# 08-MagnetSensor.net
KiCad netlist of a schematic drawn in Altium Designer
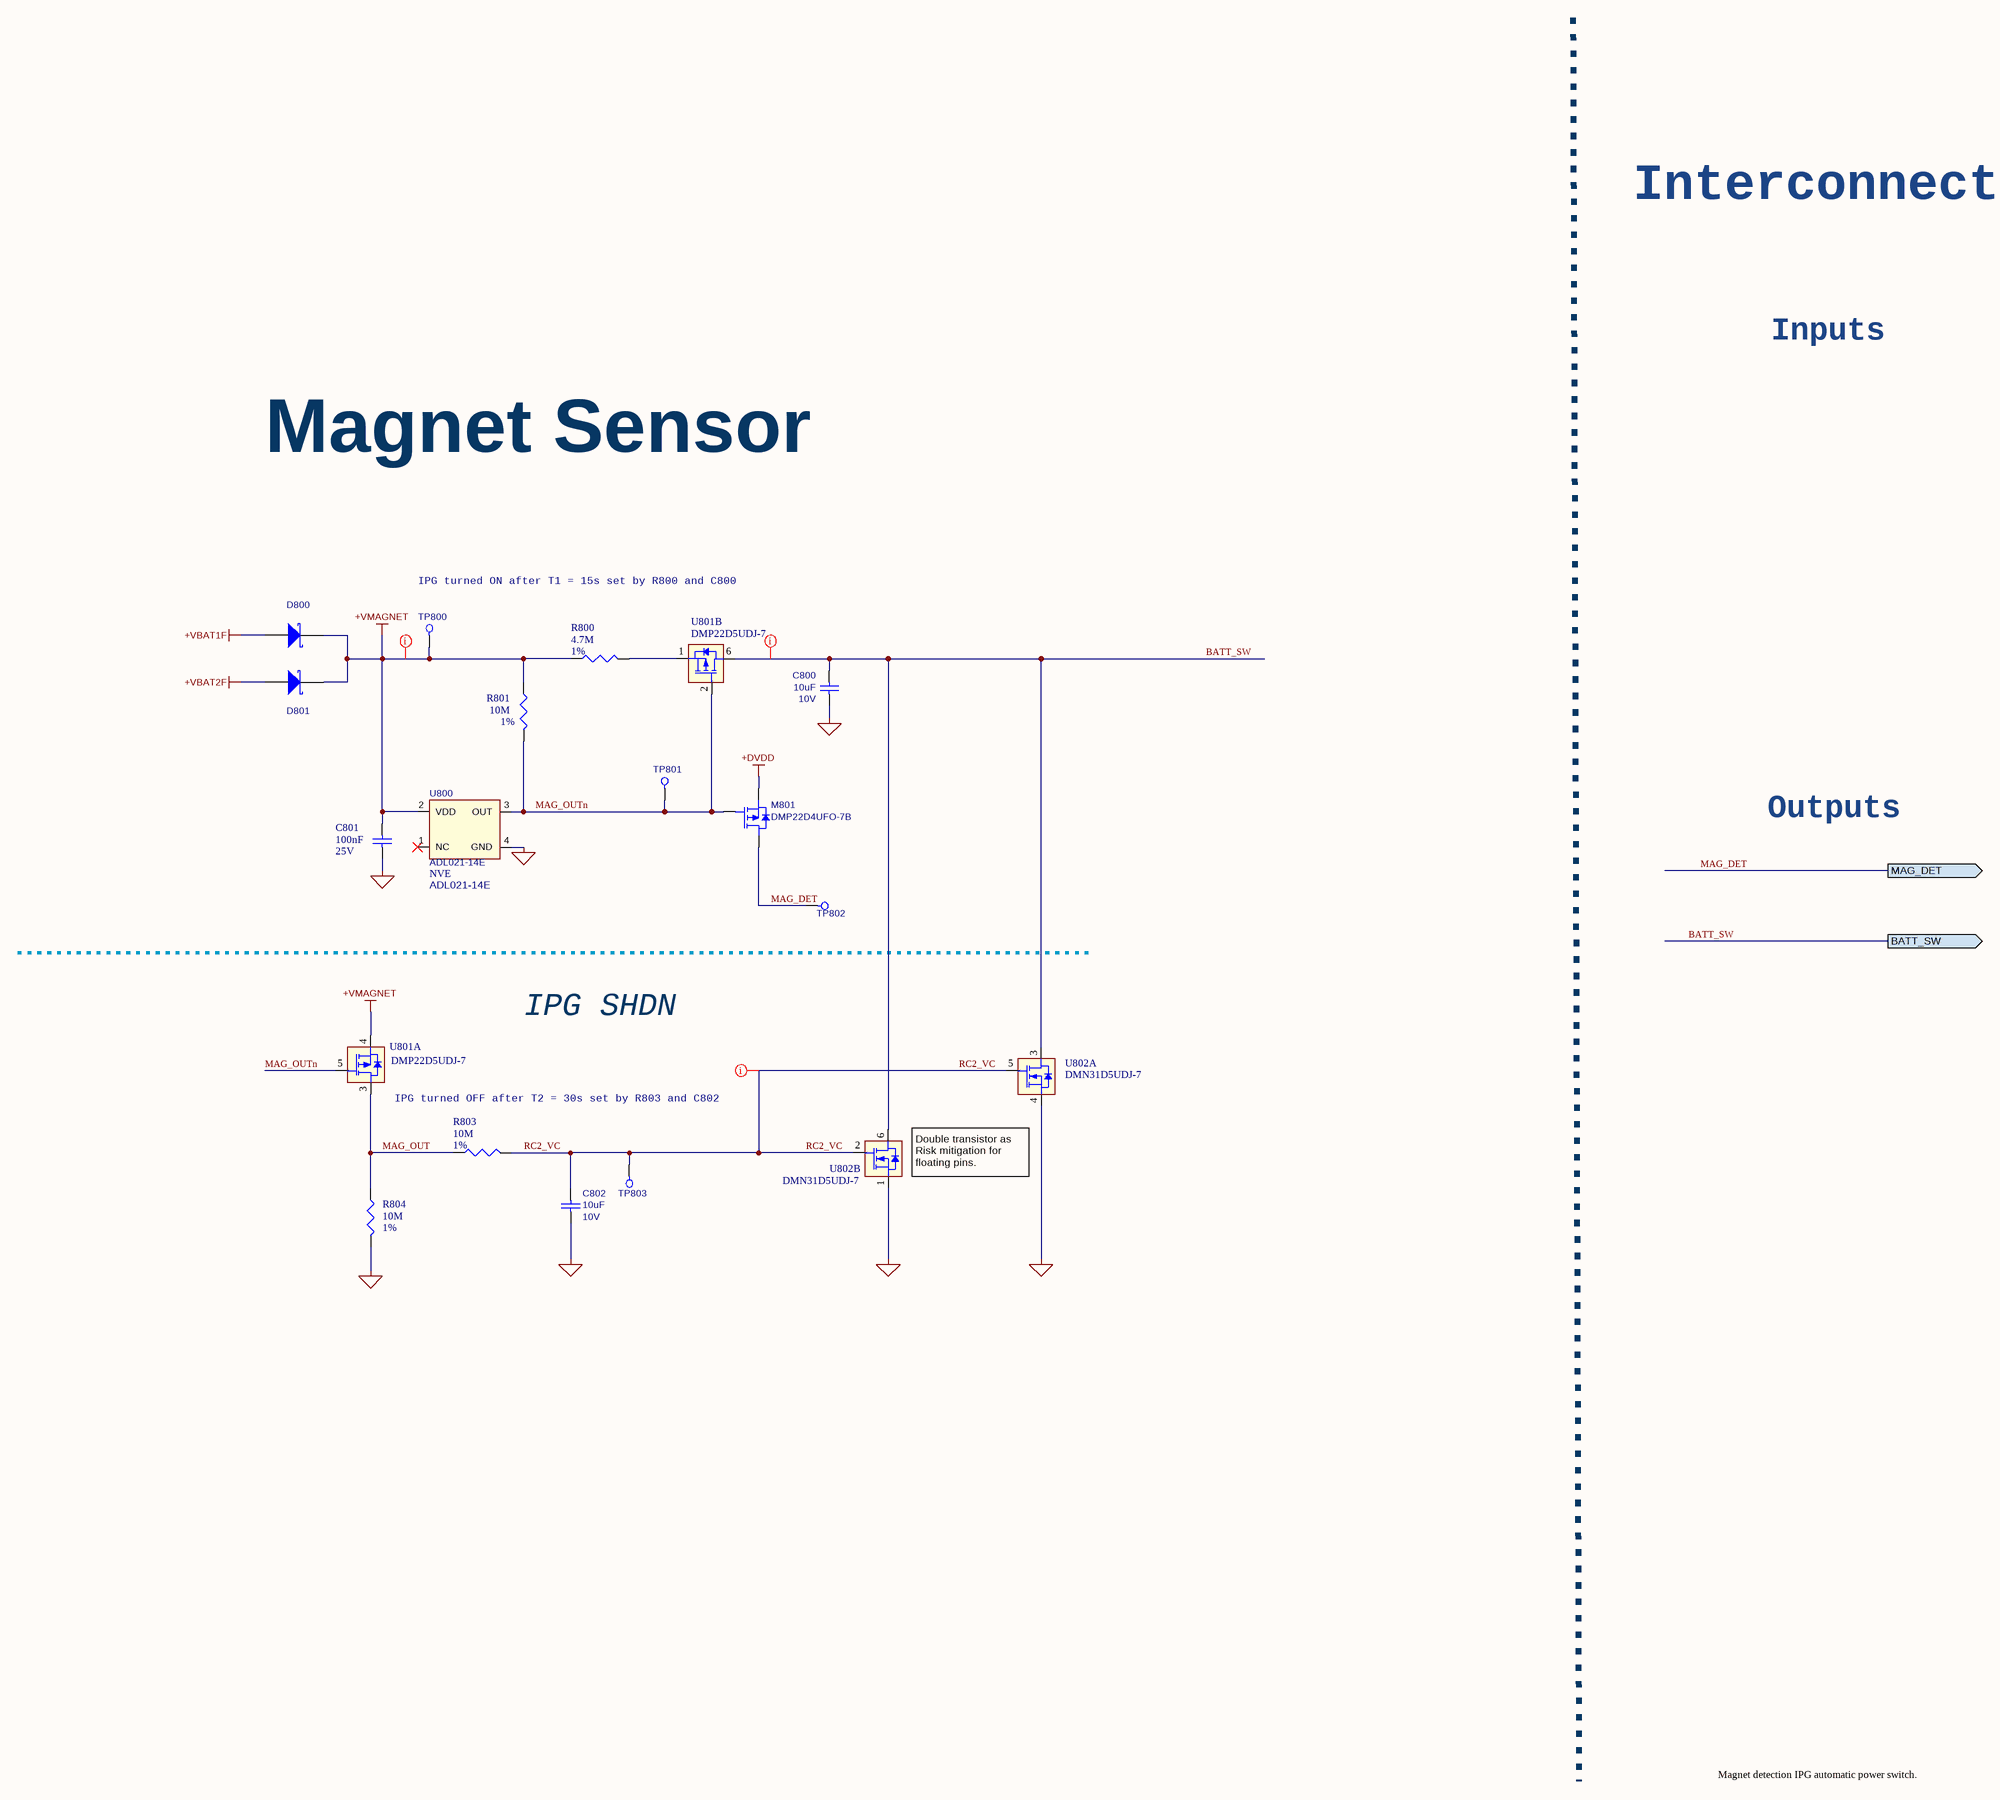
[diagram p0: 08-MagnetSensor.SchDoc]

(export (version "E")
  (design (tool "Eeschema 10.0.6"))
  (components
    (comp (ref "C800")
      (value "10uF")
      (footprint "CAP0402_REDUCED")
      (description "Capacitor, 10uf, X5R, 10V, 20%, 0402, Implant-grade")
      (fields
        (field (name "MANUFACTURER") "Murata")
        (field (name "RATING") "10V")
        (field (name "MANUFACTURER PART NUMBER") "ZRB15XR61A106ME01D")
      )
      (libsource (lib "MP-LIBRARY") (part "ZRB15XR61A106ME01D"))
    )
    (comp (ref "C801")
      (value "100nF")
      (footprint "C0201_C")
      (fields
        (field (name "MANUFACTURER") "Murata")
        (field (name "MANUFACTURER PART NUMBER") "GRM033R61E104KE14J")
        (field (name "RATED DC VOLTAGE (URDC)") "25V")
      )
      (libsource (lib "MP-LIBRARY") (part "GRM033R61E104KE14J"))
    )
    (comp (ref "C802")
      (value "10uF")
      (footprint "CAP0402_REDUCED")
      (description "Capacitor, 10uf, X5R, 10V, 20%, 0402, Implant-grade")
      (fields
        (field (name "MANUFACTURER") "Murata")
        (field (name "RATING") "10V")
        (field (name "MANUFACTURER PART NUMBER") "ZRB15XR61A106ME01D")
      )
      (libsource (lib "MP-LIBRARY") (part "ZRB15XR61A106ME01D"))
    )
    (comp (ref "D800")
      (value "NSR0130P2T5G")
      (footprint "ONSC_SOD-923_CASE514AB")
      (description "Schottky, 30V, 100mA, 385mV, 200mW, SOD-923")
      (fields (field (name "MANUFACTURER") "ON Semiconductor"))
      (libsource (lib "MP-LIBRARY") (part "NSR0130P2T5G"))
    )
    (comp (ref "D801")
      (value "NSR0130P2T5G")
      (footprint "ONSC_SOD-923_CASE514AB")
      (description "Schottky, 30V, 100mA, 385mV, 200mW, SOD-923")
      (fields (field (name "MANUFACTURER") "ON Semiconductor"))
      (libsource (lib "MP-LIBRARY") (part "NSR0130P2T5G"))
    )
    (comp (ref "M801")
      (value "DMP22D4UFO-7B")
      (footprint "DIODESINC_X2-DFN0604-3")
      (description "MOSFET, P-chan, -20V, -383mA, DFN0604")
      (fields (field (name "MANUFACTURER") "Diodes Inc"))
      (libsource (lib "MP-LIBRARY") (part "DMP22D4UFO-7B"))
    )
    (comp (ref "R800")
      (value "4.7M")
      (footprint "R0201_C")
      (fields
        (field (name "MANUFACTURER") "Vishay Dale")
        (field (name "MANUFACTURER PART NUMBER") "CRCW02014M70FNED")
        (field (name "TOLERANCE") "1%")
        (field (name "POWER") "50mW")
      )
      (libsource (lib "MP-LIBRARY") (part "CRCW02014M70FNED"))
    )
    (comp (ref "R801")
      (value "10M")
      (footprint "R0201_C")
      (fields
        (field (name "MANUFACTURER") "Vishay Draloric")
        (field (name "MANUFACTURER PART NUMBER") "CRCW020110M0FNED")
        (field (name "TOLERANCE") "1%")
        (field (name "POWER") "50mW")
      )
      (libsource (lib "MP-LIBRARY") (part "CRCW020110M0FNED"))
    )
    (comp (ref "R803")
      (value "10M")
      (footprint "R0201_C")
      (fields
        (field (name "MANUFACTURER") "Vishay Draloric")
        (field (name "MANUFACTURER PART NUMBER") "CRCW020110M0FNED")
        (field (name "TOLERANCE") "1%")
        (field (name "POWER") "50mW")
      )
      (libsource (lib "MP-LIBRARY") (part "CRCW020110M0FNED"))
    )
    (comp (ref "R804")
      (value "10M")
      (footprint "R0201_C")
      (fields
        (field (name "MANUFACTURER") "Vishay Draloric")
        (field (name "MANUFACTURER PART NUMBER") "CRCW020110M0FNED")
        (field (name "TOLERANCE") "1%")
        (field (name "POWER") "50mW")
      )
      (libsource (lib "MP-LIBRARY") (part "CRCW020110M0FNED"))
    )
    (comp (ref "TP800")
      (value "Test Point")
      (footprint "testpad_0.9mm")
      (description "Test pad, 0.90mm circular pad")
      (libsource (lib "MP-LIBRARY") (part "Test Point"))
    )
    (comp (ref "TP801")
      (value "Test Point")
      (footprint "testpad_0.9mm")
      (description "Test pad, 0.90mm circular pad")
      (libsource (lib "MP-LIBRARY") (part "Test Point"))
    )
    (comp (ref "TP802")
      (value "Test Point")
      (footprint "testpad_0.9mm")
      (description "Test pad, 0.90mm circular pad")
      (libsource (lib "MP-LIBRARY") (part "Test Point"))
    )
    (comp (ref "TP803")
      (value "Test Point")
      (footprint "testpad_0.9mm")
      (description "Test pad, 0.90mm circular pad")
      (libsource (lib "MP-LIBRARY") (part "Test Point"))
    )
    (comp (ref "U800")
      (value "ADL021-14E")
      (footprint "NVE_ULLGA4")
      (description "Magnet Sensor, 15 Gauss, ULLGA4, Implant-grade")
      (fields (field (name "MANUFACTURER") "NVE") (field (name "ALTIUM_VALUE") "ADL021-14E"))
      (libsource (lib "MP-LIBRARY") (part "ADL021-14E"))
    )
    (comp (ref "U801")
      (value "DMP22D5UDJ-7")
      (footprint "DIODESINC_SOT-963-6")
      (description "MOSFET 2P-CH 20V 0.36A SOT963")
      (fields (field (name "MANUFACTURER") "Diodes inc."))
      (libsource (lib "") (part "DMP22D5UDJ-7_1"))
    )
    (comp (ref "U802")
      (value "DMN31D5UDJ-7")
      (footprint "DIODESINC_SOT-963-6")
      (description "MOSFET 2N-CH 30V 0.22A SOT963")
      (fields (field (name "MANUFACTURER") "Diodes inc."))
      (libsource (lib "MP-LIBRARY") (part "DMN31D5UDJ-7"))
    )
  )
  (nets
    (net (code "1") (name "+DVDD") (class "Default")
      (node (ref "M801") (pin "2") (pinfunction "S_2") (pintype "passive"))
    )
    (net (code "2") (name "+VBAT1F") (class "Default")
      (node (ref "D800") (pin "2") (pinfunction "A_2") (pintype "passive"))
    )
    (net (code "3") (name "+VBAT2F") (class "Default")
      (node (ref "D801") (pin "2") (pinfunction "A_2") (pintype "passive"))
    )
    (net (code "4") (name "+VMAGNET") (class "Default")
      (node (ref "C801") (pin "2") (pinfunction "2_2") (pintype "passive"))
      (node (ref "D800") (pin "1") (pinfunction "K_1") (pintype "passive"))
      (node (ref "D801") (pin "1") (pinfunction "K_1") (pintype "passive"))
      (node (ref "R800") (pin "1") (pinfunction "1_1") (pintype "passive"))
      (node (ref "R801") (pin "1") (pinfunction "1_1") (pintype "passive"))
      (node (ref "TP800") (pin "1") (pinfunction "1_1") (pintype "passive"))
      (node (ref "U800") (pin "2") (pinfunction "VDD_2") (pintype "power_in"))
      (node (ref "U801") (pin "4") (pinfunction "4_4") (pintype "passive"))
    )
    (net (code "5") (name "/BATT_SW") (class "Default")
      (node (ref "C800") (pin "1") (pinfunction "1_1") (pintype "passive"))
      (node (ref "U801") (pin "6") (pinfunction "6_6") (pintype "passive"))
      (node (ref "U802") (pin "3") (pinfunction "3_3") (pintype "passive"))
      (node (ref "U802") (pin "6") (pinfunction "6_6") (pintype "passive"))
    )
    (net (code "6") (name "/MAG_DET") (class "Default")
      (node (ref "M801") (pin "3") (pinfunction "D_3") (pintype "passive"))
      (node (ref "TP802") (pin "1") (pinfunction "1_1") (pintype "passive"))
    )
    (net (code "7") (name "/MAG_OUT") (class "Default")
      (node (ref "R803") (pin "1") (pinfunction "1_1") (pintype "passive"))
      (node (ref "R804") (pin "1") (pinfunction "1_1") (pintype "passive"))
      (node (ref "U801") (pin "3") (pinfunction "3_3") (pintype "passive"))
    )
    (net (code "8") (name "/MAG_OUTn") (class "Default")
      (node (ref "M801") (pin "1") (pinfunction "G_1") (pintype "passive"))
      (node (ref "R801") (pin "2") (pinfunction "2_2") (pintype "passive"))
      (node (ref "TP801") (pin "1") (pinfunction "1_1") (pintype "passive"))
      (node (ref "U800") (pin "3") (pinfunction "OUT_3") (pintype "passive"))
      (node (ref "U801") (pin "2") (pinfunction "2_2") (pintype "passive"))
      (node (ref "U801") (pin "5") (pinfunction "5_5") (pintype "passive"))
    )
    (net (code "9") (name "/RC2_VC") (class "Default")
      (node (ref "C802") (pin "2") (pinfunction "2_2") (pintype "passive"))
      (node (ref "R803") (pin "2") (pinfunction "2_2") (pintype "passive"))
      (node (ref "TP803") (pin "1") (pinfunction "1_1") (pintype "passive"))
      (node (ref "U802") (pin "2") (pinfunction "2_2") (pintype "passive"))
      (node (ref "U802") (pin "5") (pinfunction "5_5") (pintype "passive"))
    )
    (net (code "10") (name "GND") (class "Default")
      (node (ref "C800") (pin "2") (pinfunction "2_2") (pintype "passive"))
      (node (ref "C801") (pin "1") (pinfunction "1_1") (pintype "passive"))
      (node (ref "C802") (pin "1") (pinfunction "1_1") (pintype "passive"))
      (node (ref "R804") (pin "2") (pinfunction "2_2") (pintype "passive"))
      (node (ref "U800") (pin "4") (pinfunction "GND_4") (pintype "power_in"))
      (node (ref "U802") (pin "1") (pinfunction "1_1") (pintype "passive"))
      (node (ref "U802") (pin "4") (pinfunction "4_4") (pintype "passive"))
    )
    (net (code "11") (name "Net-(R800-Pad2)") (class "Default")
      (node (ref "R800") (pin "2") (pinfunction "2_2") (pintype "passive"))
      (node (ref "U801") (pin "1") (pinfunction "1_1") (pintype "passive"))
    )
    (net (code "12") (name "unconnected-(U800-NC-Pad1)") (class "Default")
      (node (ref "U800") (pin "1") (pinfunction "NC_1") (pintype "passive+no_connect"))
    )
  )
)
